# MainBoard.net
KiCad netlist of a schematic drawn in EAGLE
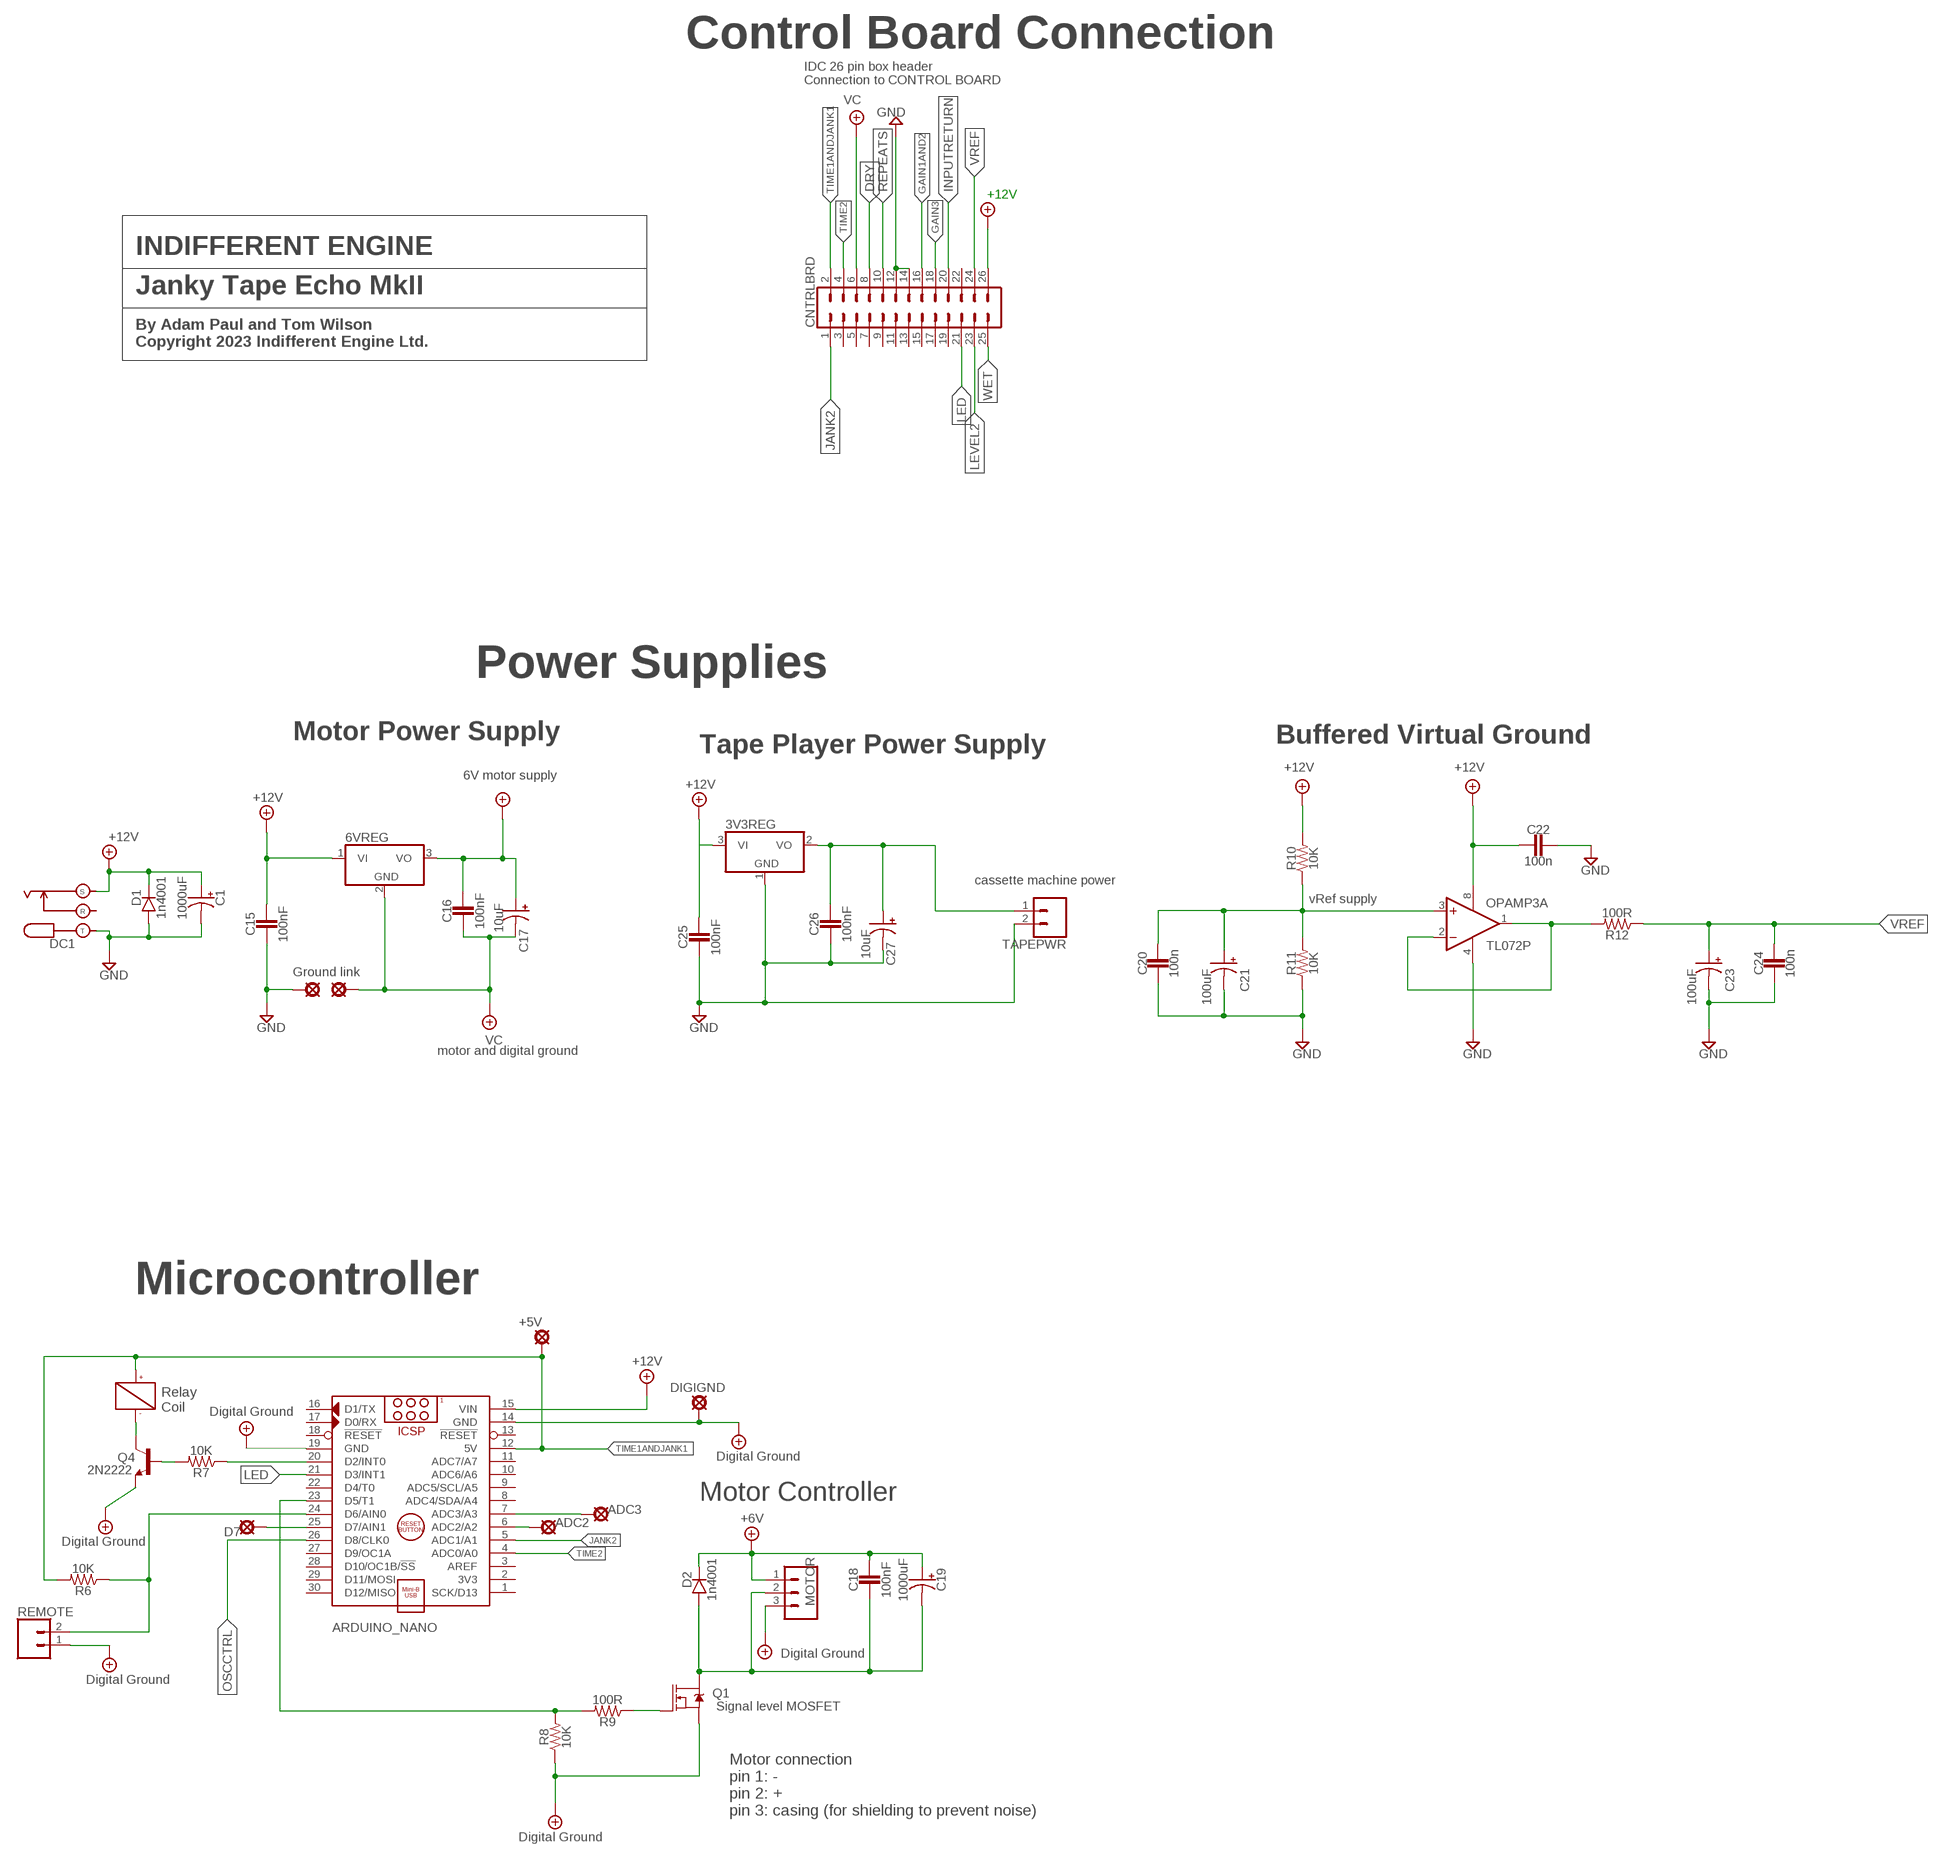
[diagram p0: schematic, sheet 1, part 1 of 2]
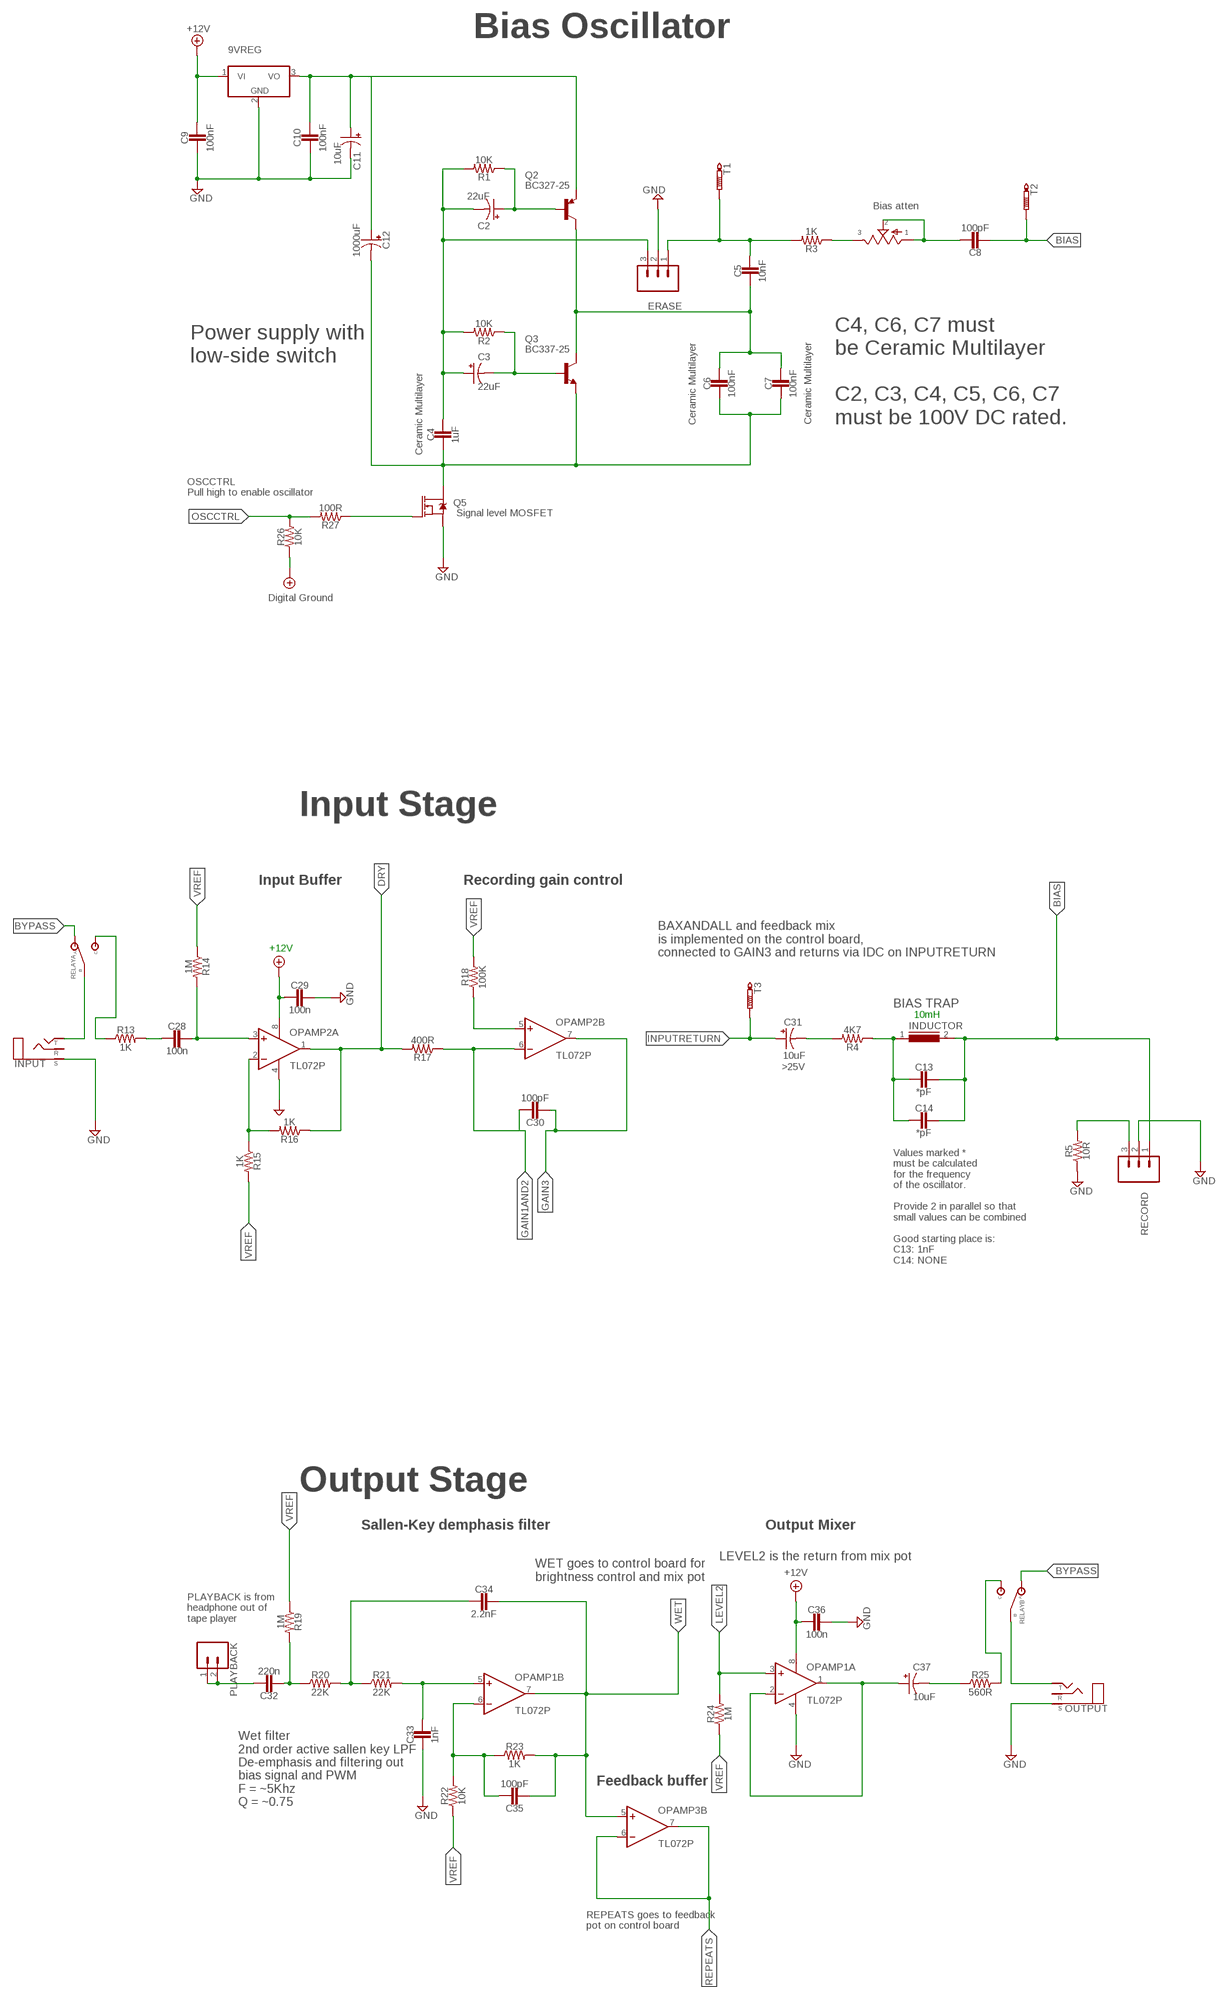
[diagram p1: schematic, sheet 1, part 2 of 2]

(export (version "E")
  (design (tool "Eeschema 10.0.6"))
  (components
    (comp (ref "+5V")
      (value "PADL")
      (footprint "eagle-import:LONG")
      (libsource (lib "eagle-import") (part "PADL"))
    )
    (comp (ref "3V3REG")
      (value "78TO220H_2_SMALL")
      (footprint "eagle-import:TO220H_SMALL")
      (libsource (lib "eagle-import") (part "78TO220H_2_SMALL"))
    )
    (comp (ref "6VREG")
      (value "78TO220H_SMALL")
      (footprint "eagle-import:TO220H_SMALL")
      (libsource (lib "eagle-import") (part "78TO220H_SMALL"))
    )
    (comp (ref "9VREG")
      (value "78TO220H_SMALL")
      (footprint "eagle-import:TO220H_SMALL")
      (libsource (lib "eagle-import") (part "78TO220H_SMALL"))
    )
    (comp (ref "ADC2")
      (value "PADL")
      (footprint "eagle-import:LONG")
      (libsource (lib "eagle-import") (part "PADL"))
    )
    (comp (ref "ADC3")
      (value "PADL")
      (footprint "eagle-import:LONG")
      (libsource (lib "eagle-import") (part "PADL"))
    )
    (comp (ref "ANALOG_GND")
      (value "PADL")
      (footprint "eagle-import:LONG")
      (libsource (lib "eagle-import") (part "PADL"))
    )
    (comp (ref "ARDUINO_NANO")
      (value "ARDUINO_NANO")
      (footprint "eagle-import:ARDUINO_NANO")
      (libsource (lib "eagle-import") (part "ARDUINO_NANO"))
    )
    (comp (ref "BIASLEVEL")
      (value "POTTRIM3/8")
      (footprint "eagle-import:B375P")
      (libsource (lib "eagle-import") (part "POTTRIM3/8"))
    )
    (comp (ref "C1")
      (value "1000uF")
      (footprint "eagle-import:080_5MM")
      (libsource (lib "eagle-import") (part "8.0_MM.2"))
    )
    (comp (ref "C2")
      (value "22uF")
      (footprint "eagle-import:050_2.5MM.1")
      (libsource (lib "eagle-import") (part "5.0_MM.3"))
    )
    (comp (ref "C3")
      (value "22uF")
      (footprint "eagle-import:050_2.5MM.1")
      (libsource (lib "eagle-import") (part "5.0_MM.3"))
    )
    (comp (ref "C4")
      (value "1uF")
      (footprint "eagle-import:5MM")
      (libsource (lib "eagle-import") (part "CAP.2"))
    )
    (comp (ref "C5")
      (value "10nF")
      (footprint "eagle-import:5MM")
      (libsource (lib "eagle-import") (part "CAP.2"))
    )
    (comp (ref "C6")
      (value "100nF")
      (footprint "eagle-import:5MM")
      (libsource (lib "eagle-import") (part "CAP.2"))
    )
    (comp (ref "C7")
      (value "100nF")
      (footprint "eagle-import:5MM")
      (libsource (lib "eagle-import") (part "CAP.2"))
    )
    (comp (ref "C8")
      (value "100pF")
      (footprint "eagle-import:.33UF+")
      (libsource (lib "eagle-import") (part "CAP.5"))
    )
    (comp (ref "C9")
      (value "100nF")
      (footprint "eagle-import:5MM")
      (libsource (lib "eagle-import") (part "CAP.2"))
    )
    (comp (ref "C10")
      (value "100nF")
      (footprint "eagle-import:5MM")
      (libsource (lib "eagle-import") (part "CAP.2"))
    )
    (comp (ref "C11")
      (value "10uF")
      (footprint "eagle-import:050_2.5MM.1")
      (libsource (lib "eagle-import") (part "5.0_MM.3"))
    )
    (comp (ref "C12")
      (value "1000uF")
      (footprint "eagle-import:080_5MM")
      (libsource (lib "eagle-import") (part "8.0_MM.2"))
    )
    (comp (ref "C13")
      (value "*pF")
      (footprint "eagle-import:.33UF+")
      (libsource (lib "eagle-import") (part "CAP.5"))
    )
    (comp (ref "C14")
      (value "*pF")
      (footprint "eagle-import:.33UF+")
      (libsource (lib "eagle-import") (part "CAP.5"))
    )
    (comp (ref "C15")
      (value "100nF")
      (footprint "eagle-import:5MM")
      (libsource (lib "eagle-import") (part "CAP.2"))
    )
    (comp (ref "C16")
      (value "100nF")
      (footprint "eagle-import:5MM")
      (libsource (lib "eagle-import") (part "CAP.2"))
    )
    (comp (ref "C17")
      (value "10uF")
      (footprint "eagle-import:050_2.5MM.1")
      (libsource (lib "eagle-import") (part "5.0_MM.3"))
    )
    (comp (ref "C18")
      (value "100nF")
      (footprint "eagle-import:.33UF+")
      (libsource (lib "eagle-import") (part "CAP.5"))
    )
    (comp (ref "C19")
      (value "1000uF")
      (footprint "eagle-import:080_5MM")
      (libsource (lib "eagle-import") (part "8.0_MM.2"))
    )
    (comp (ref "C20")
      (value "100n")
      (footprint "eagle-import:5MM")
      (libsource (lib "eagle-import") (part "CAP.2"))
    )
    (comp (ref "C21")
      (value "100uF")
      (footprint "eagle-import:050_2.5MM.1")
      (libsource (lib "eagle-import") (part "5.0_MM.3"))
    )
    (comp (ref "C22")
      (value "100n")
      (footprint "eagle-import:5MM")
      (libsource (lib "eagle-import") (part "CAP.2"))
    )
    (comp (ref "C23")
      (value "100uF")
      (footprint "eagle-import:050_2.5MM.1")
      (libsource (lib "eagle-import") (part "5.0_MM.3"))
    )
    (comp (ref "C24")
      (value "100n")
      (footprint "eagle-import:5MM")
      (libsource (lib "eagle-import") (part "CAP.2"))
    )
    (comp (ref "C25")
      (value "100nF")
      (footprint "eagle-import:5MM")
      (libsource (lib "eagle-import") (part "CAP.2"))
    )
    (comp (ref "C26")
      (value "100nF")
      (footprint "eagle-import:5MM")
      (libsource (lib "eagle-import") (part "CAP.2"))
    )
    (comp (ref "C27")
      (value "10uF")
      (footprint "eagle-import:050_2.5MM.1")
      (libsource (lib "eagle-import") (part "5.0_MM.3"))
    )
    (comp (ref "C28")
      (value "100n")
      (footprint "eagle-import:.33UF+")
      (libsource (lib "eagle-import") (part "CAP.5"))
    )
    (comp (ref "C29")
      (value "100n")
      (footprint "eagle-import:5MM")
      (libsource (lib "eagle-import") (part "CAP.2"))
    )
    (comp (ref "C30")
      (value "100pF")
      (footprint "eagle-import:.33UF+")
      (libsource (lib "eagle-import") (part "CAP.5"))
    )
    (comp (ref "C31")
      (value "10uF")
      (footprint "eagle-import:050_2.5MM.1")
      (fields (field (name "VOLTAGE") ">25V"))
      (libsource (lib "eagle-import") (part "5.0_MM.3"))
    )
    (comp (ref "C32")
      (value "220n")
      (footprint "eagle-import:.33UF+")
      (libsource (lib "eagle-import") (part "CAP.5"))
    )
    (comp (ref "C33")
      (value "1nF")
      (footprint "eagle-import:.33UF+")
      (libsource (lib "eagle-import") (part "CAP.5"))
    )
    (comp (ref "C34")
      (value "2.2nF")
      (footprint "eagle-import:.33UF+")
      (libsource (lib "eagle-import") (part "CAP.5"))
    )
    (comp (ref "C35")
      (value "100pF")
      (footprint "eagle-import:.33UF+")
      (libsource (lib "eagle-import") (part "CAP.5"))
    )
    (comp (ref "C36")
      (value "100n")
      (footprint "eagle-import:5MM")
      (libsource (lib "eagle-import") (part "CAP.2"))
    )
    (comp (ref "C37")
      (value "10uF")
      (footprint "eagle-import:050_2.5MM.1")
      (libsource (lib "eagle-import") (part "5.0_MM.3"))
    )
    (comp (ref "CNTRLBRD")
      (value "CONN_13X22X13")
      (footprint "eagle-import:2X13")
      (libsource (lib "eagle-import") (part "CONN_13X22X13"))
    )
    (comp (ref "D1")
      (value "1n4001")
      (footprint "eagle-import:DO41-3")
      (libsource (lib "eagle-import") (part "DO41.3"))
    )
    (comp (ref "D2")
      (value "1n4001")
      (footprint "eagle-import:DO41-3")
      (libsource (lib "eagle-import") (part "DO41.3"))
    )
    (comp (ref "D7")
      (value "PADL")
      (footprint "eagle-import:LONG")
      (libsource (lib "eagle-import") (part "PADL"))
    )
    (comp (ref "DC1")
      (value "DC_KOBICONN")
      (footprint "eagle-import:DC_KOBICONN")
      (libsource (lib "eagle-import") (part "DC_KOBICONN"))
    )
    (comp (ref "DIGIGND")
      (value "PADL")
      (footprint "eagle-import:LONG")
      (libsource (lib "eagle-import") (part "PADL"))
    )
    (comp (ref "DIGI_GROUND")
      (value "PADL")
      (footprint "eagle-import:LONG")
      (libsource (lib "eagle-import") (part "PADL"))
    )
    (comp (ref "ERASE")
      (value "455-1750-1-ND")
      (footprint "eagle-import:1X03")
      (libsource (lib "eagle-import") (part "CONN_03"))
    )
    (comp (ref "INDUCTOR")
      (value "82114R")
      (footprint "eagle-import:82114R")
      (libsource (lib "eagle-import") (part "82114R"))
    )
    (comp (ref "INPUT")
      (value "STEREO")
      (footprint "eagle-import:STEREO_PCB")
      (libsource (lib "eagle-import") (part "STEREO"))
    )
    (comp (ref "MOTOR")
      (value "455-1750-1-ND")
      (footprint "eagle-import:1X03")
      (libsource (lib "eagle-import") (part "CONN_03"))
    )
    (comp (ref "OPAMP1")
      (value "TL072P")
      (footprint "eagle-import:DIL08")
      (libsource (lib "eagle-import") (part "TL072P"))
    )
    (comp (ref "OPAMP2")
      (value "TL072P")
      (footprint "eagle-import:DIL08")
      (libsource (lib "eagle-import") (part "TL072P"))
    )
    (comp (ref "OPAMP3")
      (value "TL072P")
      (footprint "eagle-import:DIL08")
      (libsource (lib "eagle-import") (part "TL072P"))
    )
    (comp (ref "OUTPUT")
      (value "STEREO")
      (footprint "eagle-import:STEREO_PCB")
      (libsource (lib "eagle-import") (part "STEREO"))
    )
    (comp (ref "PLAYBACK")
      (value "CONN_02")
      (footprint "eagle-import:1X02")
      (libsource (lib "eagle-import") (part "CONN_02"))
    )
    (comp (ref "Q1")
      (value "60V/32A/35mΩ")
      (footprint "eagle-import:TO220V")
      (libsource (lib "eagle-import") (part "MOSFET-NCH-FQP30N06L"))
    )
    (comp (ref "Q2")
      (value "BC327-25")
      (footprint "eagle-import:TO92-EBC")
      (libsource (lib "eagle-import") (part "BC327-25"))
    )
    (comp (ref "Q3")
      (value "BC337-25TO92")
      (footprint "eagle-import:TO92-EBC")
      (libsource (lib "eagle-import") (part "BC337TO92-25"))
    )
    (comp (ref "Q4")
      (value "2N2222")
      (footprint "eagle-import:TO92-")
      (libsource (lib "eagle-import") (part "2N2222"))
    )
    (comp (ref "Q5")
      (value "60V/32A/35mΩ")
      (footprint "eagle-import:TO220V")
      (libsource (lib "eagle-import") (part "MOSFET-NCH-FQP30N06L"))
    )
    (comp (ref "R1")
      (value "10K")
      (footprint "eagle-import:7.5MM.2")
      (libsource (lib "eagle-import") (part "R.3B"))
    )
    (comp (ref "R2")
      (value "10K")
      (footprint "eagle-import:7.5MM.2")
      (libsource (lib "eagle-import") (part "R.3B"))
    )
    (comp (ref "R3")
      (value "1K")
      (footprint "eagle-import:7.5MM.2")
      (libsource (lib "eagle-import") (part "R.3B"))
    )
    (comp (ref "R4")
      (value "4K7")
      (footprint "eagle-import:7.5MM.2")
      (libsource (lib "eagle-import") (part "R.3B"))
    )
    (comp (ref "R5")
      (value "10R")
      (footprint "eagle-import:7.5MM.2")
      (libsource (lib "eagle-import") (part "R.3B"))
    )
    (comp (ref "R6")
      (value "10K")
      (footprint "eagle-import:7.5MM.2")
      (libsource (lib "eagle-import") (part "R.3B"))
    )
    (comp (ref "R7")
      (value "10K")
      (footprint "eagle-import:7.5MM.2")
      (libsource (lib "eagle-import") (part "R.3B"))
    )
    (comp (ref "R8")
      (value "10K")
      (footprint "eagle-import:7.5MM.2")
      (libsource (lib "eagle-import") (part "R.3B"))
    )
    (comp (ref "R9")
      (value "100R")
      (footprint "eagle-import:7.5MM.2")
      (libsource (lib "eagle-import") (part "R.3B"))
    )
    (comp (ref "R10")
      (value "10K")
      (footprint "eagle-import:7.5MM.2")
      (libsource (lib "eagle-import") (part "R.3B"))
    )
    (comp (ref "R11")
      (value "10K")
      (footprint "eagle-import:7.5MM.2")
      (libsource (lib "eagle-import") (part "R.3B"))
    )
    (comp (ref "R12")
      (value "100R")
      (footprint "eagle-import:7.5MM.2")
      (libsource (lib "eagle-import") (part "R.3B"))
    )
    (comp (ref "R13")
      (value "1K")
      (footprint "eagle-import:7.5MM.2")
      (libsource (lib "eagle-import") (part "R.3B"))
    )
    (comp (ref "R14")
      (value "1M")
      (footprint "eagle-import:7.5MM.2")
      (libsource (lib "eagle-import") (part "R.3B"))
    )
    (comp (ref "R15")
      (value "1K")
      (footprint "eagle-import:7.5MM.2")
      (libsource (lib "eagle-import") (part "R.3B"))
    )
    (comp (ref "R16")
      (value "1K")
      (footprint "eagle-import:7.5MM.2")
      (libsource (lib "eagle-import") (part "R.3B"))
    )
    (comp (ref "R17")
      (value "400R")
      (footprint "eagle-import:7.5MM.2")
      (libsource (lib "eagle-import") (part "R.3B"))
    )
    (comp (ref "R18")
      (value "100K")
      (footprint "eagle-import:7.5MM.2")
      (libsource (lib "eagle-import") (part "R.3B"))
    )
    (comp (ref "R19")
      (value "1M")
      (footprint "eagle-import:7.5MM.2")
      (libsource (lib "eagle-import") (part "R.3B"))
    )
    (comp (ref "R20")
      (value "22K")
      (footprint "eagle-import:7.5MM.2")
      (libsource (lib "eagle-import") (part "R.3B"))
    )
    (comp (ref "R21")
      (value "22K")
      (footprint "eagle-import:7.5MM.2")
      (libsource (lib "eagle-import") (part "R.3B"))
    )
    (comp (ref "R22")
      (value "10K")
      (footprint "eagle-import:7.5MM.2")
      (libsource (lib "eagle-import") (part "R.3B"))
    )
    (comp (ref "R23")
      (value "1K")
      (footprint "eagle-import:7.5MM.2")
      (libsource (lib "eagle-import") (part "R.3B"))
    )
    (comp (ref "R24")
      (value "1M")
      (footprint "eagle-import:7.5MM.2")
      (libsource (lib "eagle-import") (part "R.3B"))
    )
    (comp (ref "R25")
      (value "560R")
      (footprint "eagle-import:7.5MM.2")
      (libsource (lib "eagle-import") (part "R.3B"))
    )
    (comp (ref "R26")
      (value "10K")
      (footprint "eagle-import:7.5MM.2")
      (libsource (lib "eagle-import") (part "R.3B"))
    )
    (comp (ref "R27")
      (value "100R")
      (footprint "eagle-import:7.5MM.2")
      (libsource (lib "eagle-import") (part "R.3B"))
    )
    (comp (ref "RECORD")
      (value "455-1750-1-ND")
      (footprint "eagle-import:1X03")
      (libsource (lib "eagle-import") (part "CONN_03"))
    )
    (comp (ref "RELAY")
      (value "IM02TSIM02TS")
      (footprint "eagle-import:8-PIN")
      (libsource (lib "eagle-import") (part "IM02TSIM02TS"))
    )
    (comp (ref "REMOTE")
      (value "CONN_02")
      (footprint "eagle-import:1X02")
      (libsource (lib "eagle-import") (part "CONN_02"))
    )
    (comp (ref "T1")
      (value "PTR1B2,54")
      (footprint "eagle-import:B2,54")
      (libsource (lib "eagle-import") (part "PTR1B2,54"))
    )
    (comp (ref "T2")
      (value "PTR1B2,54")
      (footprint "eagle-import:B2,54")
      (libsource (lib "eagle-import") (part "PTR1B2,54"))
    )
    (comp (ref "T3")
      (value "PTR1B2,54")
      (footprint "eagle-import:B2,54")
      (libsource (lib "eagle-import") (part "PTR1B2,54"))
    )
    (comp (ref "TAPEPWR")
      (value "CONN_02")
      (footprint "eagle-import:1X02")
      (libsource (lib "eagle-import") (part "CONN_02"))
    )
  )
  (nets
    (net (code "1") (name "+9V") (class "Default")
      (node (ref "3V3REG") (pin "3") (pinfunction "VI_3") (pintype "input"))
      (node (ref "6VREG") (pin "1") (pinfunction "VI_1") (pintype "input"))
      (node (ref "9VREG") (pin "1") (pinfunction "VI_1") (pintype "input"))
      (node (ref "ARDUINO_NANO") (pin "15") (pinfunction "VIN_15") (pintype "power_in"))
      (node (ref "C1") (pin "+") (pinfunction "+_+") (pintype "passive"))
      (node (ref "C15") (pin "1") (pinfunction "1_1") (pintype "passive"))
      (node (ref "C22") (pin "2") (pinfunction "2_2") (pintype "passive"))
      (node (ref "C25") (pin "1") (pinfunction "1_1") (pintype "passive"))
      (node (ref "C29") (pin "2") (pinfunction "2_2") (pintype "passive"))
      (node (ref "C36") (pin "2") (pinfunction "2_2") (pintype "passive"))
      (node (ref "C9") (pin "1") (pinfunction "1_1") (pintype "passive"))
      (node (ref "CNTRLBRD") (pin "26") (pinfunction "26_26") (pintype "passive"))
      (node (ref "D1") (pin "C") (pinfunction "C_C") (pintype "passive"))
      (node (ref "DC1") (pin "S") (pinfunction "S_S") (pintype "bidirectional"))
      (node (ref "OPAMP1") (pin "8") (pinfunction "V+_8") (pintype "power_in"))
      (node (ref "OPAMP2") (pin "8") (pinfunction "V+_8") (pintype "power_in"))
      (node (ref "OPAMP3") (pin "8") (pinfunction "V+_8") (pintype "power_in"))
      (node (ref "R10") (pin "2") (pinfunction "2_2") (pintype "passive"))
    )
    (net (code "2") (name "BIAS") (class "Default")
      (node (ref "C13") (pin "1") (pinfunction "1_1") (pintype "passive"))
      (node (ref "C14") (pin "1") (pinfunction "1_1") (pintype "passive"))
      (node (ref "C8") (pin "2") (pinfunction "2_2") (pintype "passive"))
      (node (ref "INDUCTOR") (pin "2") (pinfunction "2_2") (pintype "passive"))
      (node (ref "RECORD") (pin "1") (pinfunction "1_1") (pintype "passive"))
      (node (ref "T2") (pin "TP") (pinfunction "TP_TP") (pintype "input"))
    )
    (net (code "3") (name "BYPASS") (class "Default")
      (node (ref "RELAY") (pin "10") (pinfunction "A_10") (pintype "passive"))
      (node (ref "RELAY") (pin "3") (pinfunction "A_3") (pintype "passive"))
    )
    (net (code "4") (name "DRY") (class "Default")
      (node (ref "CNTRLBRD") (pin "8") (pinfunction "8_8") (pintype "passive"))
      (node (ref "OPAMP2") (pin "1") (pinfunction "OUT_1") (pintype "output"))
      (node (ref "R16") (pin "1") (pinfunction "1_1") (pintype "passive"))
      (node (ref "R17") (pin "2") (pinfunction "2_2") (pintype "passive"))
    )
    (net (code "5") (name "GAIN1AND2") (class "Default")
      (node (ref "C30") (pin "1") (pinfunction "1_1") (pintype "passive"))
      (node (ref "CNTRLBRD") (pin "16") (pinfunction "16_16") (pintype "passive"))
      (node (ref "OPAMP2") (pin "6") (pinfunction "-IN_6") (pintype "input"))
      (node (ref "R17") (pin "1") (pinfunction "1_1") (pintype "passive"))
    )
    (net (code "6") (name "GAIN3") (class "Default")
      (node (ref "C30") (pin "2") (pinfunction "2_2") (pintype "passive"))
      (node (ref "CNTRLBRD") (pin "18") (pinfunction "18_18") (pintype "passive"))
      (node (ref "OPAMP2") (pin "7") (pinfunction "OUT_7") (pintype "output"))
    )
    (net (code "7") (name "GND") (class "Default")
      (node (ref "3V3REG") (pin "1") (pinfunction "GND_1") (pintype "passive"))
      (node (ref "9VREG") (pin "2") (pinfunction "GND_2") (pintype "passive"))
      (node (ref "ANALOG_GND") (pin "1") (pinfunction "PAD_1") (pintype "passive"))
      (node (ref "C1") (pin "-") (pinfunction "-_-") (pintype "passive"))
      (node (ref "C10") (pin "2") (pinfunction "2_2") (pintype "passive"))
      (node (ref "C11") (pin "-") (pinfunction "-_-") (pintype "passive"))
      (node (ref "C15") (pin "2") (pinfunction "2_2") (pintype "passive"))
      (node (ref "C20") (pin "2") (pinfunction "2_2") (pintype "passive"))
      (node (ref "C21") (pin "-") (pinfunction "-_-") (pintype "passive"))
      (node (ref "C22") (pin "1") (pinfunction "1_1") (pintype "passive"))
      (node (ref "C23") (pin "-") (pinfunction "-_-") (pintype "passive"))
      (node (ref "C24") (pin "2") (pinfunction "2_2") (pintype "passive"))
      (node (ref "C25") (pin "2") (pinfunction "2_2") (pintype "passive"))
      (node (ref "C26") (pin "2") (pinfunction "2_2") (pintype "passive"))
      (node (ref "C27") (pin "-") (pinfunction "-_-") (pintype "passive"))
      (node (ref "C29") (pin "1") (pinfunction "1_1") (pintype "passive"))
      (node (ref "C33") (pin "2") (pinfunction "2_2") (pintype "passive"))
      (node (ref "C36") (pin "1") (pinfunction "1_1") (pintype "passive"))
      (node (ref "C9") (pin "2") (pinfunction "2_2") (pintype "passive"))
      (node (ref "CNTRLBRD") (pin "12") (pinfunction "12_12") (pintype "passive"))
      (node (ref "CNTRLBRD") (pin "14") (pinfunction "14_14") (pintype "passive"))
      (node (ref "D1") (pin "A") (pinfunction "A_A") (pintype "passive"))
      (node (ref "DC1") (pin "T") (pinfunction "T_T") (pintype "bidirectional"))
      (node (ref "ERASE") (pin "2") (pinfunction "2_2") (pintype "passive"))
      (node (ref "INPUT") (pin "P$1") (pinfunction "S_P$1") (pintype "passive"))
      (node (ref "OPAMP1") (pin "4") (pinfunction "V-_4") (pintype "power_in"))
      (node (ref "OPAMP2") (pin "4") (pinfunction "V-_4") (pintype "power_in"))
      (node (ref "OPAMP3") (pin "4") (pinfunction "V-_4") (pintype "power_in"))
      (node (ref "OUTPUT") (pin "P$1") (pinfunction "S_P$1") (pintype "passive"))
      (node (ref "Q5") (pin "3") (pinfunction "S_3") (pintype "bidirectional"))
      (node (ref "R11") (pin "1") (pinfunction "1_1") (pintype "passive"))
      (node (ref "R5") (pin "1") (pinfunction "1_1") (pintype "passive"))
      (node (ref "RECORD") (pin "2") (pinfunction "2_2") (pintype "passive"))
      (node (ref "TAPEPWR") (pin "2") (pinfunction "2_2") (pintype "passive"))
    )
    (net (code "8") (name "INPUTRETURN") (class "Default")
      (node (ref "C31") (pin "+") (pinfunction "+_+") (pintype "passive"))
      (node (ref "CNTRLBRD") (pin "20") (pinfunction "20_20") (pintype "passive"))
      (node (ref "T3") (pin "TP") (pinfunction "TP_TP") (pintype "input"))
    )
    (net (code "9") (name "JANK2") (class "Default")
      (node (ref "ARDUINO_NANO") (pin "5") (pinfunction "ADC1/A1_5") (pintype "bidirectional"))
      (node (ref "CNTRLBRD") (pin "1") (pinfunction "1_1") (pintype "passive"))
    )
    (net (code "10") (name "LED") (class "Default")
      (node (ref "ARDUINO_NANO") (pin "21") (pinfunction "D3/INT1_21") (pintype "bidirectional"))
      (node (ref "CNTRLBRD") (pin "21") (pinfunction "21_21") (pintype "passive"))
    )
    (net (code "11") (name "LEVEL2") (class "Default")
      (node (ref "CNTRLBRD") (pin "23") (pinfunction "23_23") (pintype "passive"))
      (node (ref "OPAMP1") (pin "3") (pinfunction "+IN_3") (pintype "input"))
      (node (ref "R24") (pin "2") (pinfunction "2_2") (pintype "passive"))
    )
    (net (code "12") (name "Net-(3V3REG-VO)") (class "Default")
      (node (ref "3V3REG") (pin "2") (pinfunction "VO_2") (pintype "passive"))
      (node (ref "C26") (pin "1") (pinfunction "1_1") (pintype "passive"))
      (node (ref "C27") (pin "+") (pinfunction "+_+") (pintype "passive"))
      (node (ref "TAPEPWR") (pin "1") (pinfunction "1_1") (pintype "passive"))
    )
    (net (code "13") (name "Net-(9VREG-VO)") (class "Default")
      (node (ref "9VREG") (pin "3") (pinfunction "VO_3") (pintype "passive"))
      (node (ref "C10") (pin "1") (pinfunction "1_1") (pintype "passive"))
      (node (ref "C11") (pin "+") (pinfunction "+_+") (pintype "passive"))
      (node (ref "C12") (pin "+") (pinfunction "+_+") (pintype "passive"))
      (node (ref "Q2") (pin "E") (pinfunction "E_E") (pintype "passive"))
    )
    (net (code "14") (name "Net-(ADC2-PAD)") (class "Default")
      (node (ref "ADC2") (pin "1") (pinfunction "PAD_1") (pintype "passive"))
      (node (ref "ARDUINO_NANO") (pin "6") (pinfunction "ADC2/A2_6") (pintype "bidirectional"))
    )
    (net (code "15") (name "Net-(ADC3-PAD)") (class "Default")
      (node (ref "ADC3") (pin "1") (pinfunction "PAD_1") (pintype "passive"))
      (node (ref "ARDUINO_NANO") (pin "7") (pinfunction "ADC3/A3_7") (pintype "bidirectional"))
    )
    (net (code "16") (name "Net-(ARDUINO_NANO-D2{slash}INT0)") (class "Default")
      (node (ref "ARDUINO_NANO") (pin "20") (pinfunction "D2/INT0_20") (pintype "bidirectional"))
      (node (ref "R7") (pin "1") (pinfunction "1_1") (pintype "passive"))
    )
    (net (code "17") (name "Net-(ARDUINO_NANO-D5{slash}T1)") (class "Default")
      (node (ref "ARDUINO_NANO") (pin "23") (pinfunction "D5/T1_23") (pintype "bidirectional"))
      (node (ref "R8") (pin "2") (pinfunction "2_2") (pintype "passive"))
      (node (ref "R9") (pin "2") (pinfunction "2_2") (pintype "passive"))
    )
    (net (code "18") (name "Net-(ARDUINO_NANO-D6{slash}AIN0)") (class "Default")
      (node (ref "ARDUINO_NANO") (pin "24") (pinfunction "D6/AIN0_24") (pintype "bidirectional"))
      (node (ref "R6") (pin "1") (pinfunction "1_1") (pintype "passive"))
      (node (ref "REMOTE") (pin "2") (pinfunction "2_2") (pintype "passive"))
    )
    (net (code "19") (name "Net-(ARDUINO_NANO-D7{slash}AIN1)") (class "Default")
      (node (ref "ARDUINO_NANO") (pin "25") (pinfunction "D7/AIN1_25") (pintype "bidirectional"))
      (node (ref "D7") (pin "1") (pinfunction "PAD_1") (pintype "passive"))
    )
    (net (code "20") (name "Net-(BIASLEVEL-Pad1)") (class "Default")
      (node (ref "BIASLEVEL") (pin "1") (pinfunction "1_1") (pintype "passive"))
      (node (ref "BIASLEVEL") (pin "2") (pinfunction "2_2") (pintype "passive"))
      (node (ref "C8") (pin "1") (pinfunction "1_1") (pintype "passive"))
    )
    (net (code "21") (name "Net-(BIASLEVEL-Pad3)") (class "Default")
      (node (ref "BIASLEVEL") (pin "3") (pinfunction "3_3") (pintype "passive"))
      (node (ref "R3") (pin "1") (pinfunction "1_1") (pintype "passive"))
    )
    (net (code "22") (name "Net-(C2-Pad+)") (class "Default")
      (node (ref "C2") (pin "+") (pinfunction "+_+") (pintype "passive"))
      (node (ref "Q2") (pin "B") (pinfunction "B_B") (pintype "passive"))
      (node (ref "R1") (pin "1") (pinfunction "1_1") (pintype "passive"))
    )
    (net (code "23") (name "Net-(C2-Pad-)") (class "Default")
      (node (ref "C2") (pin "-") (pinfunction "-_-") (pintype "passive"))
      (node (ref "C3") (pin "+") (pinfunction "+_+") (pintype "passive"))
      (node (ref "C4") (pin "1") (pinfunction "1_1") (pintype "passive"))
      (node (ref "ERASE") (pin "3") (pinfunction "3_3") (pintype "passive"))
      (node (ref "R1") (pin "2") (pinfunction "2_2") (pintype "passive"))
      (node (ref "R2") (pin "2") (pinfunction "2_2") (pintype "passive"))
    )
    (net (code "24") (name "Net-(C3-Pad-)") (class "Default")
      (node (ref "C3") (pin "-") (pinfunction "-_-") (pintype "passive"))
      (node (ref "Q3") (pin "B") (pinfunction "B_B") (pintype "passive"))
      (node (ref "R2") (pin "1") (pinfunction "1_1") (pintype "passive"))
    )
    (net (code "25") (name "Net-(C5-Pad1)") (class "Default")
      (node (ref "C5") (pin "1") (pinfunction "1_1") (pintype "passive"))
      (node (ref "ERASE") (pin "1") (pinfunction "1_1") (pintype "passive"))
      (node (ref "R3") (pin "2") (pinfunction "2_2") (pintype "passive"))
      (node (ref "T1") (pin "TP") (pinfunction "TP_TP") (pintype "input"))
    )
    (net (code "26") (name "Net-(C5-Pad2)") (class "Default")
      (node (ref "C5") (pin "2") (pinfunction "2_2") (pintype "passive"))
      (node (ref "C6") (pin "1") (pinfunction "1_1") (pintype "passive"))
      (node (ref "C7") (pin "1") (pinfunction "1_1") (pintype "passive"))
      (node (ref "Q2") (pin "C") (pinfunction "C_C") (pintype "passive"))
      (node (ref "Q3") (pin "C") (pinfunction "C_C") (pintype "passive"))
    )
    (net (code "27") (name "Net-(C13-Pad2)") (class "Default")
      (node (ref "C13") (pin "2") (pinfunction "2_2") (pintype "passive"))
      (node (ref "C14") (pin "2") (pinfunction "2_2") (pintype "passive"))
      (node (ref "INDUCTOR") (pin "1") (pinfunction "1_1") (pintype "passive"))
      (node (ref "R4") (pin "1") (pinfunction "1_1") (pintype "passive"))
    )
    (net (code "28") (name "Net-(C28-Pad2)") (class "Default")
      (node (ref "C28") (pin "2") (pinfunction "2_2") (pintype "passive"))
      (node (ref "R13") (pin "2") (pinfunction "2_2") (pintype "passive"))
    )
    (net (code "29") (name "Net-(C31-Pad-)") (class "Default")
      (node (ref "C31") (pin "-") (pinfunction "-_-") (pintype "passive"))
      (node (ref "R4") (pin "2") (pinfunction "2_2") (pintype "passive"))
    )
    (net (code "30") (name "Net-(C32-Pad1)") (class "Default")
      (node (ref "C32") (pin "1") (pinfunction "1_1") (pintype "passive"))
      (node (ref "PLAYBACK") (pin "1") (pinfunction "1_1") (pintype "passive"))
      (node (ref "PLAYBACK") (pin "2") (pinfunction "2_2") (pintype "passive"))
    )
    (net (code "31") (name "Net-(C32-Pad2)") (class "Default")
      (node (ref "C32") (pin "2") (pinfunction "2_2") (pintype "passive"))
      (node (ref "R19") (pin "2") (pinfunction "2_2") (pintype "passive"))
      (node (ref "R20") (pin "1") (pinfunction "1_1") (pintype "passive"))
    )
    (net (code "32") (name "Net-(C34-Pad2)") (class "Default")
      (node (ref "C34") (pin "2") (pinfunction "2_2") (pintype "passive"))
      (node (ref "R20") (pin "2") (pinfunction "2_2") (pintype "passive"))
      (node (ref "R21") (pin "1") (pinfunction "1_1") (pintype "passive"))
    )
    (net (code "33") (name "Net-(C37-Pad-)") (class "Default")
      (node (ref "C37") (pin "-") (pinfunction "-_-") (pintype "passive"))
      (node (ref "R25") (pin "1") (pinfunction "1_1") (pintype "passive"))
    )
    (net (code "34") (name "Net-(INPUT-T)") (class "Default")
      (node (ref "INPUT") (pin "P$3") (pinfunction "T_P$3") (pintype "passive"))
      (node (ref "RELAY") (pin "4") (pinfunction "B_4") (pintype "passive"))
    )
    (net (code "35") (name "Net-(OPAMP1A--IN)") (class "Default")
      (node (ref "C37") (pin "+") (pinfunction "+_+") (pintype "passive"))
      (node (ref "OPAMP1") (pin "1") (pinfunction "OUT_1") (pintype "output"))
      (node (ref "OPAMP1") (pin "2") (pinfunction "-IN_2") (pintype "input"))
    )
    (net (code "36") (name "Net-(OPAMP1B-+IN)") (class "Default")
      (node (ref "C33") (pin "1") (pinfunction "1_1") (pintype "passive"))
      (node (ref "OPAMP1") (pin "5") (pinfunction "+IN_5") (pintype "input"))
      (node (ref "R21") (pin "2") (pinfunction "2_2") (pintype "passive"))
    )
    (net (code "37") (name "Net-(OPAMP1B--IN)") (class "Default")
      (node (ref "C35") (pin "1") (pinfunction "1_1") (pintype "passive"))
      (node (ref "OPAMP1") (pin "6") (pinfunction "-IN_6") (pintype "input"))
      (node (ref "R22") (pin "2") (pinfunction "2_2") (pintype "passive"))
      (node (ref "R23") (pin "1") (pinfunction "1_1") (pintype "passive"))
    )
    (net (code "38") (name "Net-(OPAMP2A-+IN)") (class "Default")
      (node (ref "C28") (pin "1") (pinfunction "1_1") (pintype "passive"))
      (node (ref "OPAMP2") (pin "3") (pinfunction "+IN_3") (pintype "input"))
      (node (ref "R14") (pin "2") (pinfunction "2_2") (pintype "passive"))
    )
    (net (code "39") (name "Net-(OPAMP2A--IN)") (class "Default")
      (node (ref "OPAMP2") (pin "2") (pinfunction "-IN_2") (pintype "input"))
      (node (ref "R15") (pin "1") (pinfunction "1_1") (pintype "passive"))
      (node (ref "R16") (pin "2") (pinfunction "2_2") (pintype "passive"))
    )
    (net (code "40") (name "Net-(OPAMP2B-+IN)") (class "Default")
      (node (ref "OPAMP2") (pin "5") (pinfunction "+IN_5") (pintype "input"))
      (node (ref "R18") (pin "1") (pinfunction "1_1") (pintype "passive"))
    )
    (net (code "41") (name "Net-(OPAMP3A-+IN)") (class "Default")
      (node (ref "C20") (pin "1") (pinfunction "1_1") (pintype "passive"))
      (node (ref "C21") (pin "+") (pinfunction "+_+") (pintype "passive"))
      (node (ref "OPAMP3") (pin "3") (pinfunction "+IN_3") (pintype "input"))
      (node (ref "R10") (pin "1") (pinfunction "1_1") (pintype "passive"))
      (node (ref "R11") (pin "2") (pinfunction "2_2") (pintype "passive"))
    )
    (net (code "42") (name "Net-(OPAMP3A--IN)") (class "Default")
      (node (ref "OPAMP3") (pin "1") (pinfunction "OUT_1") (pintype "output"))
      (node (ref "OPAMP3") (pin "2") (pinfunction "-IN_2") (pintype "input"))
      (node (ref "R12") (pin "2") (pinfunction "2_2") (pintype "passive"))
    )
    (net (code "43") (name "Net-(OUTPUT-T)") (class "Default")
      (node (ref "OUTPUT") (pin "P$3") (pinfunction "T_P$3") (pintype "passive"))
      (node (ref "RELAY") (pin "9") (pinfunction "B_9") (pintype "passive"))
    )
    (net (code "44") (name "Net-(Q1-D)") (class "Default")
      (node (ref "C18") (pin "2") (pinfunction "2_2") (pintype "passive"))
      (node (ref "C19") (pin "-") (pinfunction "-_-") (pintype "passive"))
      (node (ref "D2") (pin "A") (pinfunction "A_A") (pintype "passive"))
      (node (ref "MOTOR") (pin "2") (pinfunction "2_2") (pintype "passive"))
      (node (ref "Q1") (pin "2") (pinfunction "D_2") (pintype "bidirectional"))
    )
    (net (code "45") (name "Net-(Q1-G)") (class "Default")
      (node (ref "Q1") (pin "1") (pinfunction "G_1") (pintype "bidirectional"))
      (node (ref "R9") (pin "1") (pinfunction "1_1") (pintype "passive"))
    )
    (net (code "46") (name "Net-(Q4-B)") (class "Default")
      (node (ref "Q4") (pin "2") (pinfunction "B_2") (pintype "passive"))
      (node (ref "R7") (pin "2") (pinfunction "2_2") (pintype "passive"))
    )
    (net (code "47") (name "Net-(Q4-C)") (class "Default")
      (node (ref "Q4") (pin "1") (pinfunction "C_1") (pintype "passive"))
      (node (ref "RELAY") (pin "1") (pinfunction "-_1") (pintype "bidirectional"))
    )
    (net (code "48") (name "Net-(Q5-D)") (class "Default")
      (node (ref "C12") (pin "-") (pinfunction "-_-") (pintype "passive"))
      (node (ref "C4") (pin "2") (pinfunction "2_2") (pintype "passive"))
      (node (ref "C6") (pin "2") (pinfunction "2_2") (pintype "passive"))
      (node (ref "C7") (pin "2") (pinfunction "2_2") (pintype "passive"))
      (node (ref "Q3") (pin "E") (pinfunction "E_E") (pintype "passive"))
      (node (ref "Q5") (pin "2") (pinfunction "D_2") (pintype "bidirectional"))
    )
    (net (code "49") (name "Net-(Q5-G)") (class "Default")
      (node (ref "Q5") (pin "1") (pinfunction "G_1") (pintype "bidirectional"))
      (node (ref "R27") (pin "1") (pinfunction "1_1") (pintype "passive"))
    )
    (net (code "50") (name "Net-(R5-Pad2)") (class "Default")
      (node (ref "R5") (pin "2") (pinfunction "2_2") (pintype "passive"))
      (node (ref "RECORD") (pin "3") (pinfunction "3_3") (pintype "passive"))
    )
    (net (code "51") (name "Net-(RELAYA-C)") (class "Default")
      (node (ref "R13") (pin "1") (pinfunction "1_1") (pintype "passive"))
      (node (ref "RELAY") (pin "5") (pinfunction "C_5") (pintype "passive"))
    )
    (net (code "52") (name "Net-(RELAYB-C)") (class "Default")
      (node (ref "R25") (pin "2") (pinfunction "2_2") (pintype "passive"))
      (node (ref "RELAY") (pin "8") (pinfunction "C_8") (pintype "passive"))
    )
    (net (code "53") (name "OSCCTRL") (class "Default")
      (node (ref "ARDUINO_NANO") (pin "26") (pinfunction "D8/CLK0_26") (pintype "bidirectional"))
      (node (ref "R26") (pin "2") (pinfunction "2_2") (pintype "passive"))
      (node (ref "R27") (pin "2") (pinfunction "2_2") (pintype "passive"))
    )
    (net (code "54") (name "REPEATS") (class "Default")
      (node (ref "CNTRLBRD") (pin "10") (pinfunction "10_10") (pintype "passive"))
      (node (ref "OPAMP3") (pin "6") (pinfunction "-IN_6") (pintype "input"))
      (node (ref "OPAMP3") (pin "7") (pinfunction "OUT_7") (pintype "output"))
    )
    (net (code "55") (name "TIME1ANDJANK1") (class "Default")
      (node (ref "+5V") (pin "1") (pinfunction "PAD_1") (pintype "passive"))
      (node (ref "ARDUINO_NANO") (pin "12") (pinfunction "5V_12") (pintype "power_in"))
      (node (ref "CNTRLBRD") (pin "2") (pinfunction "2_2") (pintype "passive"))
      (node (ref "R6") (pin "2") (pinfunction "2_2") (pintype "passive"))
      (node (ref "RELAY") (pin "12") (pinfunction "+_12") (pintype "bidirectional"))
    )
    (net (code "56") (name "TIME2") (class "Default")
      (node (ref "ARDUINO_NANO") (pin "4") (pinfunction "ADC0/A0_4") (pintype "bidirectional"))
      (node (ref "CNTRLBRD") (pin "4") (pinfunction "4_4") (pintype "passive"))
    )
    (net (code "57") (name "VC") (class "Default")
      (node (ref "6VREG") (pin "2") (pinfunction "GND_2") (pintype "passive"))
      (node (ref "ARDUINO_NANO") (pin "14") (pinfunction "GND_14") (pintype "power_in"))
      (node (ref "ARDUINO_NANO") (pin "19") (pinfunction "GND_19") (pintype "power_in"))
      (node (ref "C16") (pin "2") (pinfunction "2_2") (pintype "passive"))
      (node (ref "C17") (pin "-") (pinfunction "-_-") (pintype "passive"))
      (node (ref "CNTRLBRD") (pin "6") (pinfunction "6_6") (pintype "passive"))
      (node (ref "DIGIGND") (pin "1") (pinfunction "PAD_1") (pintype "passive"))
      (node (ref "DIGI_GROUND") (pin "1") (pinfunction "PAD_1") (pintype "passive"))
      (node (ref "MOTOR") (pin "3") (pinfunction "3_3") (pintype "passive"))
      (node (ref "Q1") (pin "3") (pinfunction "S_3") (pintype "bidirectional"))
      (node (ref "Q4") (pin "3") (pinfunction "E_3") (pintype "passive"))
      (node (ref "R26") (pin "1") (pinfunction "1_1") (pintype "passive"))
      (node (ref "R8") (pin "1") (pinfunction "1_1") (pintype "passive"))
      (node (ref "REMOTE") (pin "1") (pinfunction "1_1") (pintype "passive"))
    )
    (net (code "58") (name "VD") (class "Default")
      (node (ref "6VREG") (pin "3") (pinfunction "VO_3") (pintype "passive"))
      (node (ref "C16") (pin "1") (pinfunction "1_1") (pintype "passive"))
      (node (ref "C17") (pin "+") (pinfunction "+_+") (pintype "passive"))
      (node (ref "C18") (pin "1") (pinfunction "1_1") (pintype "passive"))
      (node (ref "C19") (pin "+") (pinfunction "+_+") (pintype "passive"))
      (node (ref "D2") (pin "C") (pinfunction "C_C") (pintype "passive"))
      (node (ref "MOTOR") (pin "1") (pinfunction "1_1") (pintype "passive"))
    )
    (net (code "59") (name "VREF") (class "Default")
      (node (ref "C23") (pin "+") (pinfunction "+_+") (pintype "passive"))
      (node (ref "C24") (pin "1") (pinfunction "1_1") (pintype "passive"))
      (node (ref "CNTRLBRD") (pin "24") (pinfunction "24_24") (pintype "passive"))
      (node (ref "R12") (pin "1") (pinfunction "1_1") (pintype "passive"))
      (node (ref "R14") (pin "1") (pinfunction "1_1") (pintype "passive"))
      (node (ref "R15") (pin "2") (pinfunction "2_2") (pintype "passive"))
      (node (ref "R18") (pin "2") (pinfunction "2_2") (pintype "passive"))
      (node (ref "R19") (pin "1") (pinfunction "1_1") (pintype "passive"))
      (node (ref "R22") (pin "1") (pinfunction "1_1") (pintype "passive"))
      (node (ref "R24") (pin "1") (pinfunction "1_1") (pintype "passive"))
    )
    (net (code "60") (name "WET") (class "Default")
      (node (ref "C34") (pin "1") (pinfunction "1_1") (pintype "passive"))
      (node (ref "C35") (pin "2") (pinfunction "2_2") (pintype "passive"))
      (node (ref "CNTRLBRD") (pin "25") (pinfunction "25_25") (pintype "passive"))
      (node (ref "OPAMP1") (pin "7") (pinfunction "OUT_7") (pintype "output"))
      (node (ref "OPAMP3") (pin "5") (pinfunction "+IN_5") (pintype "input"))
      (node (ref "R23") (pin "2") (pinfunction "2_2") (pintype "passive"))
    )
    (net (code "61") (name "unconnected-(ARDUINO_NANO-3V3-Pad2)") (class "Default")
      (node (ref "ARDUINO_NANO") (pin "2") (pinfunction "3V3_2") (pintype "output"))
    )
    (net (code "62") (name "unconnected-(ARDUINO_NANO-ADC4{slash}SDA{slash}A4-Pad8)") (class "Default")
      (node (ref "ARDUINO_NANO") (pin "8") (pinfunction "ADC4/SDA/A4_8") (pintype "bidirectional"))
    )
    (net (code "63") (name "unconnected-(ARDUINO_NANO-ADC5{slash}SCL{slash}A5-Pad9)") (class "Default")
      (node (ref "ARDUINO_NANO") (pin "9") (pinfunction "ADC5/SCL/A5_9") (pintype "bidirectional"))
    )
    (net (code "64") (name "unconnected-(ARDUINO_NANO-ADC6{slash}A6-Pad10)") (class "Default")
      (node (ref "ARDUINO_NANO") (pin "10") (pinfunction "ADC6/A6_10") (pintype "bidirectional"))
    )
    (net (code "65") (name "unconnected-(ARDUINO_NANO-ADC7{slash}A7-Pad11)") (class "Default")
      (node (ref "ARDUINO_NANO") (pin "11") (pinfunction "ADC7/A7_11") (pintype "bidirectional"))
    )
    (net (code "66") (name "unconnected-(ARDUINO_NANO-AREF-Pad3)") (class "Default")
      (node (ref "ARDUINO_NANO") (pin "3") (pinfunction "AREF_3") (pintype "input"))
    )
    (net (code "67") (name "unconnected-(ARDUINO_NANO-D0{slash}RX-Pad17)") (class "Default")
      (node (ref "ARDUINO_NANO") (pin "17") (pinfunction "D0/RX_17") (pintype "bidirectional"))
    )
    (net (code "68") (name "unconnected-(ARDUINO_NANO-D1{slash}TX-Pad16)") (class "Default")
      (node (ref "ARDUINO_NANO") (pin "16") (pinfunction "D1/TX_16") (pintype "bidirectional"))
    )
    (net (code "69") (name "unconnected-(ARDUINO_NANO-D4{slash}T0-Pad22)") (class "Default")
      (node (ref "ARDUINO_NANO") (pin "22") (pinfunction "D4/T0_22") (pintype "bidirectional"))
    )
    (net (code "70") (name "unconnected-(ARDUINO_NANO-D9{slash}OC1A-Pad27)") (class "Default")
      (node (ref "ARDUINO_NANO") (pin "27") (pinfunction "D9/OC1A_27") (pintype "bidirectional"))
    )
    (net (code "71") (name "unconnected-(ARDUINO_NANO-D10{slash}OC1B{slash}~{SS}-Pad28)") (class "Default")
      (node (ref "ARDUINO_NANO") (pin "28") (pinfunction "D10/OC1B/~{SS}_28") (pintype "bidirectional"))
    )
    (net (code "72") (name "unconnected-(ARDUINO_NANO-D11{slash}MOSI-Pad29)") (class "Default")
      (node (ref "ARDUINO_NANO") (pin "29") (pinfunction "D11/MOSI_29") (pintype "bidirectional"))
    )
    (net (code "73") (name "unconnected-(ARDUINO_NANO-D12{slash}MISO-Pad30)") (class "Default")
      (node (ref "ARDUINO_NANO") (pin "30") (pinfunction "D12/MISO_30") (pintype "bidirectional"))
    )
    (net (code "74") (name "unconnected-(ARDUINO_NANO-SCK{slash}D13-Pad1)") (class "Default")
      (node (ref "ARDUINO_NANO") (pin "1") (pinfunction "SCK/D13_1") (pintype "bidirectional"))
    )
    (net (code "75") (name "unconnected-(ARDUINO_NANO-~{RESET}-Pad13)") (class "Default")
      (node (ref "ARDUINO_NANO") (pin "13") (pinfunction "~{RESET}_13") (pintype "input"))
    )
    (net (code "76") (name "unconnected-(ARDUINO_NANO-~{RESET}-Pad18)") (class "Default")
      (node (ref "ARDUINO_NANO") (pin "18") (pinfunction "~{RESET}_18") (pintype "input"))
    )
    (net (code "77") (name "unconnected-(CNTRLBRD-Pad3)") (class "Default")
      (node (ref "CNTRLBRD") (pin "3") (pinfunction "3_3") (pintype "passive"))
    )
    (net (code "78") (name "unconnected-(CNTRLBRD-Pad5)") (class "Default")
      (node (ref "CNTRLBRD") (pin "5") (pinfunction "5_5") (pintype "passive"))
    )
    (net (code "79") (name "unconnected-(CNTRLBRD-Pad7)") (class "Default")
      (node (ref "CNTRLBRD") (pin "7") (pinfunction "7_7") (pintype "passive"))
    )
    (net (code "80") (name "unconnected-(CNTRLBRD-Pad9)") (class "Default")
      (node (ref "CNTRLBRD") (pin "9") (pinfunction "9_9") (pintype "passive"))
    )
    (net (code "81") (name "unconnected-(CNTRLBRD-Pad11)") (class "Default")
      (node (ref "CNTRLBRD") (pin "11") (pinfunction "11_11") (pintype "passive"))
    )
    (net (code "82") (name "unconnected-(CNTRLBRD-Pad13)") (class "Default")
      (node (ref "CNTRLBRD") (pin "13") (pinfunction "13_13") (pintype "passive"))
    )
    (net (code "83") (name "unconnected-(CNTRLBRD-Pad15)") (class "Default")
      (node (ref "CNTRLBRD") (pin "15") (pinfunction "15_15") (pintype "passive"))
    )
    (net (code "84") (name "unconnected-(CNTRLBRD-Pad17)") (class "Default")
      (node (ref "CNTRLBRD") (pin "17") (pinfunction "17_17") (pintype "passive"))
    )
    (net (code "85") (name "unconnected-(CNTRLBRD-Pad19)") (class "Default")
      (node (ref "CNTRLBRD") (pin "19") (pinfunction "19_19") (pintype "passive"))
    )
    (net (code "86") (name "unconnected-(CNTRLBRD-Pad22)") (class "Default")
      (node (ref "CNTRLBRD") (pin "22") (pinfunction "22_22") (pintype "passive"))
    )
    (net (code "87") (name "unconnected-(DC1-PadR)") (class "Default")
      (node (ref "DC1") (pin "R") (pinfunction "R_R") (pintype "bidirectional"))
    )
    (net (code "88") (name "unconnected-(INPUT-R-PadP$2)") (class "Default")
      (node (ref "INPUT") (pin "P$2") (pinfunction "R_P$2") (pintype "passive"))
    )
    (net (code "89") (name "unconnected-(OUTPUT-R-PadP$2)") (class "Default")
      (node (ref "OUTPUT") (pin "P$2") (pinfunction "R_P$2") (pintype "passive"))
    )
  )
)
